# GTStoppuhr.net
KiCad netlist of a schematic drawn in EasyEDA Pro
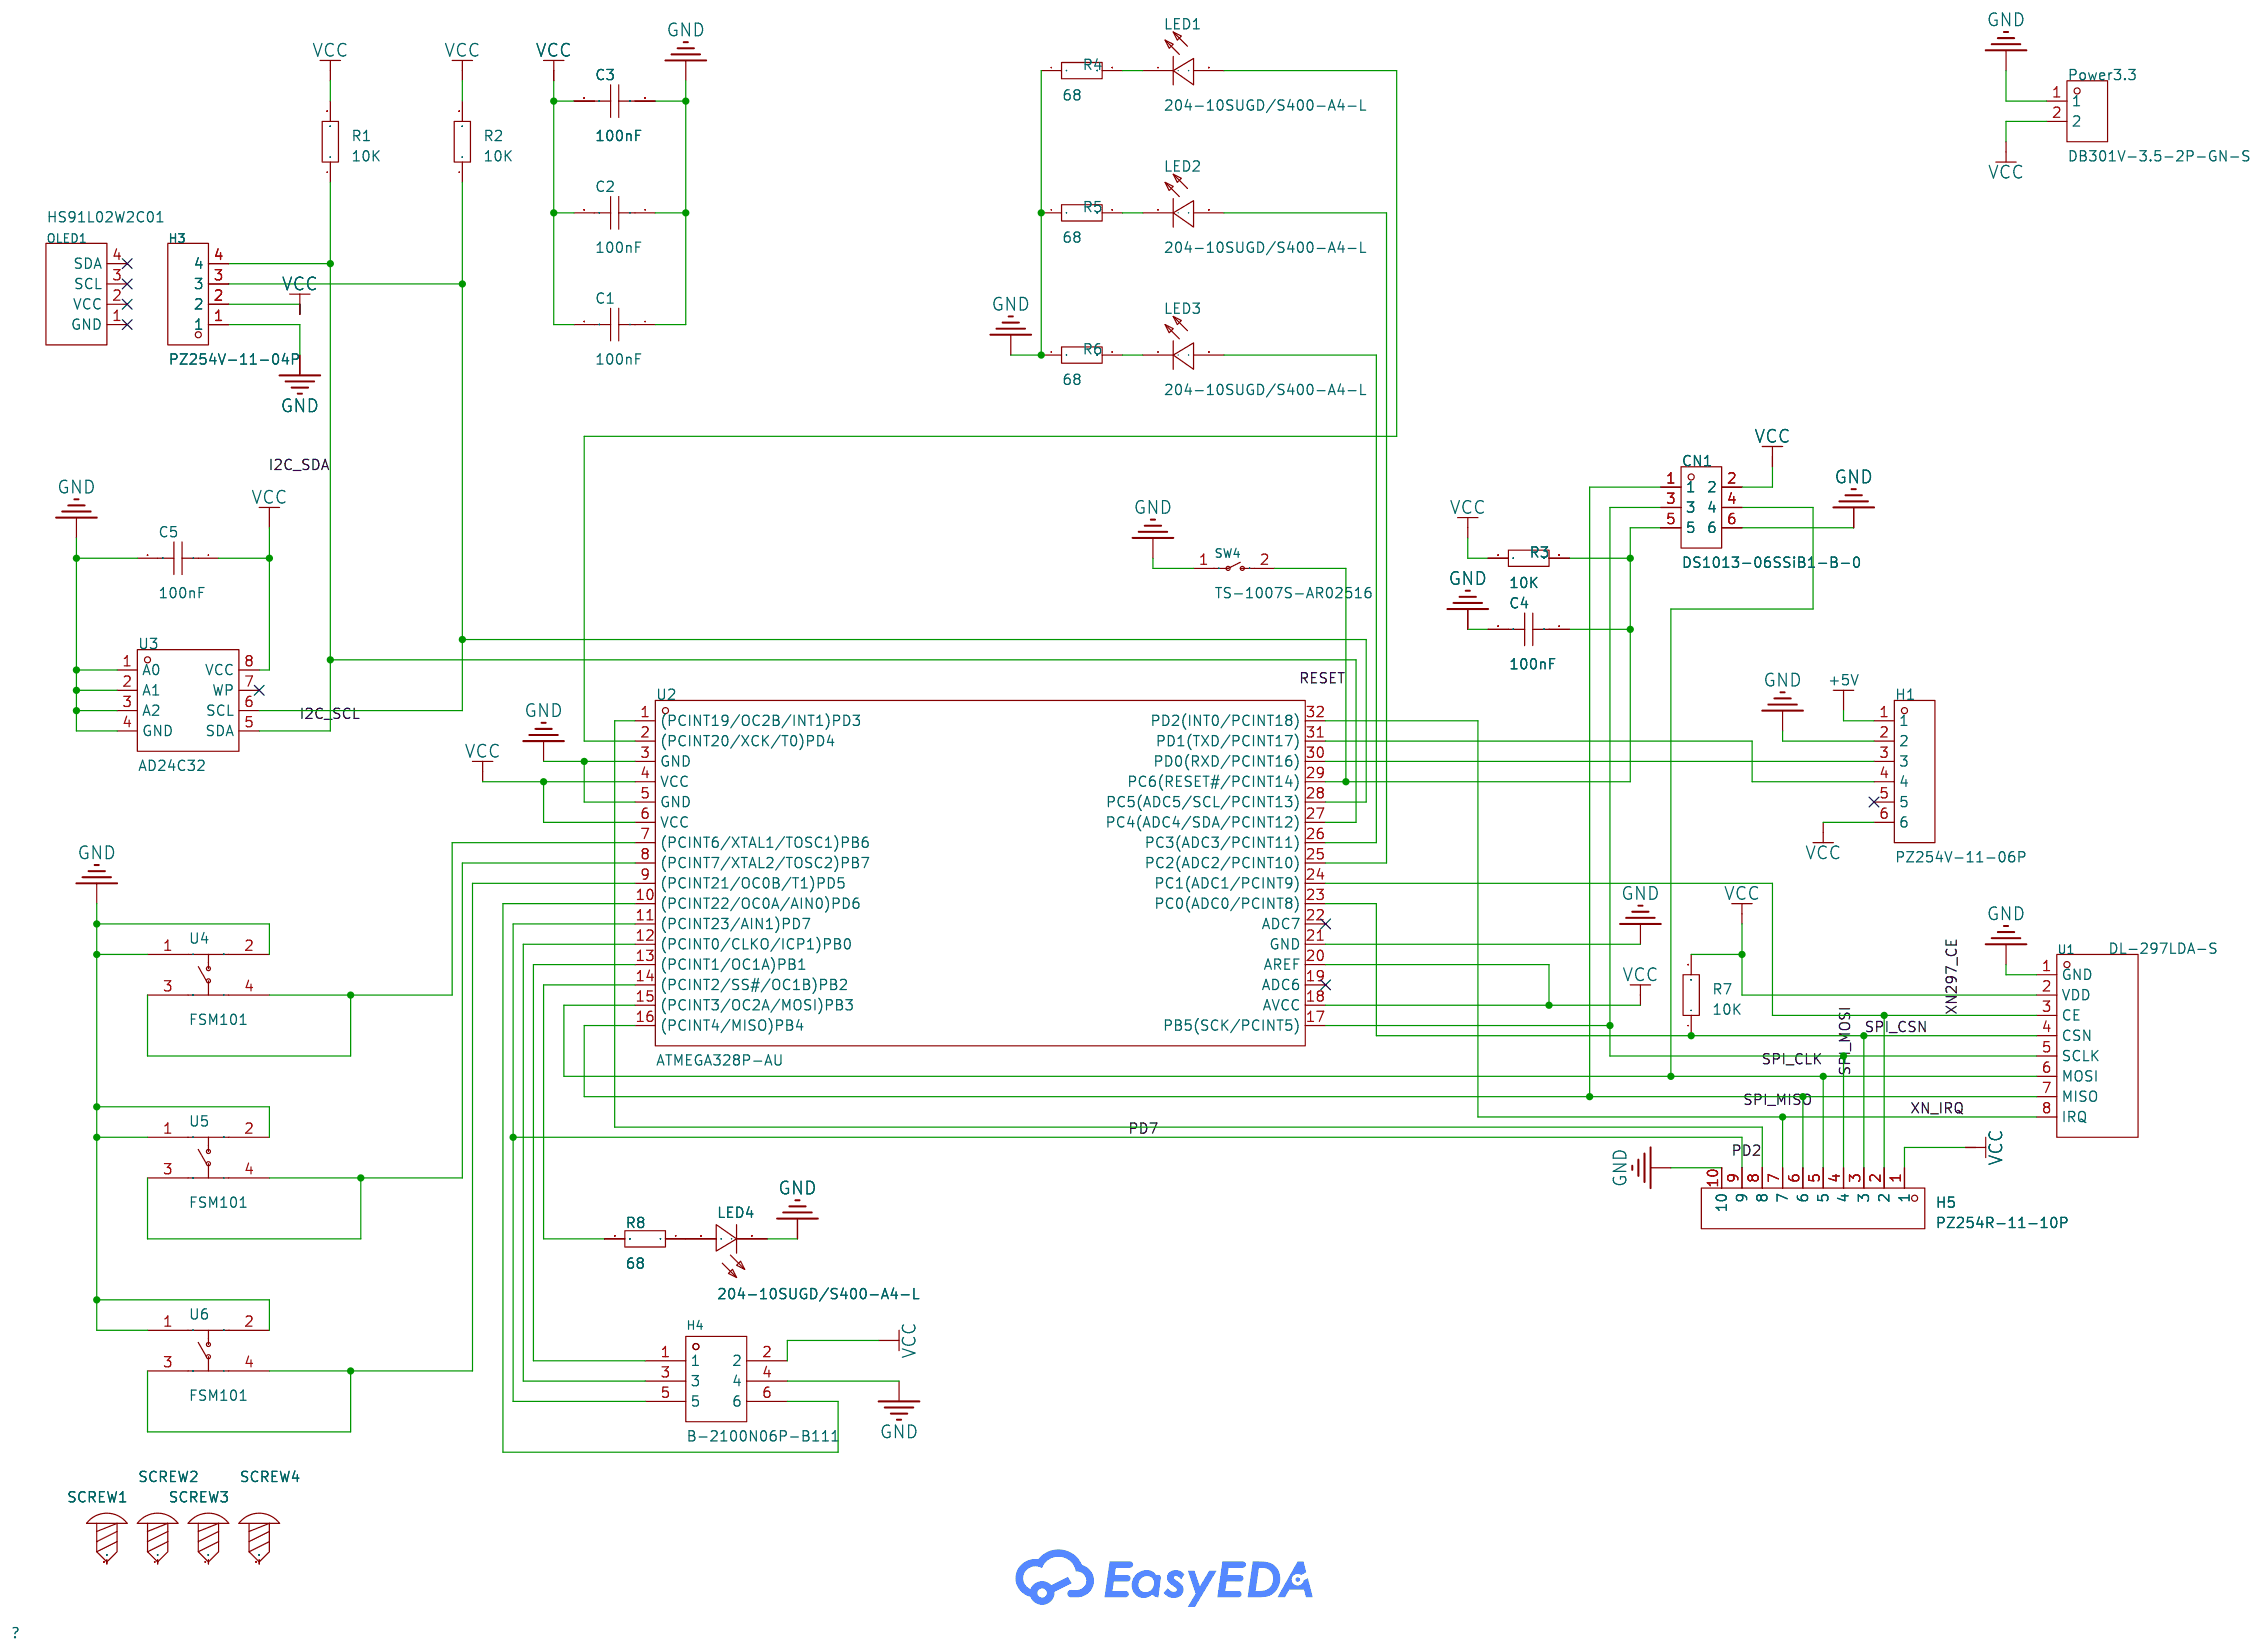
[diagram p0: schematic sheet]

(export (version "E")
  (design (tool "Eeschema 10.0.6"))
  (components
    (comp (ref "C1")
      (value "100nF")
      (footprint "easyedapro:C0603")
      (libsource (lib "easyedapro") (part "CAP"))
    )
    (comp (ref "C2")
      (value "100nF")
      (footprint "easyedapro:C0603")
      (libsource (lib "easyedapro") (part "CAP"))
    )
    (comp (ref "C3")
      (value "100nF")
      (footprint "easyedapro:C0603")
      (libsource (lib "easyedapro") (part "CAP"))
    )
    (comp (ref "C4")
      (value "100nF")
      (footprint "easyedapro:C0603")
      (libsource (lib "easyedapro") (part "CAP"))
    )
    (comp (ref "C5")
      (value "100nF")
      (footprint "easyedapro:C0603")
      (libsource (lib "easyedapro") (part "CAP"))
    )
    (comp (ref "CN1")
      (value "DS1013-06SSiB1-B-0")
      (footprint "easyedapro:IDC-TH_6P-P2.54_DS1013-06SSIB1-B-0")
      (fields (field (name "Manufacturer") "CONNFLY"))
      (libsource (lib "easyedapro") (part "DS1013-06SSIB1-B-0"))
    )
    (comp (ref "H1")
      (value "PZ254V-11-06P")
      (footprint "easyedapro:HDR-TH_6P-P2.54-V-M")
      (fields (field (name "Manufacturer") "XFCN(兴飞)"))
      (libsource (lib "easyedapro") (part "PZ254V-11-06P"))
    )
    (comp (ref "H3")
      (value "PZ254V-11-04P")
      (footprint "easyedapro:HDR-TH_4P-P2.54-V-M")
      (fields (field (name "Manufacturer") "XFCN(兴飞)"))
      (libsource (lib "easyedapro") (part "PZ254V-11-04P_C2691448"))
    )
    (comp (ref "H4")
      (value "B-2100N06P-B111")
      (footprint "easyedapro:HDR-SMD_6P-P2.54-V-M-R2-C3-S2.54-LS7.3")
      (fields (field (name "Manufacturer") "Ckmtw(灿科盟)"))
      (libsource (lib "easyedapro") (part "210SMT-2*3P Gold-plated black"))
    )
    (comp (ref "H5")
      (value "PZ254R-11-10P")
      (footprint "easyedapro:HDR-TH_10P-P2.54-H-M-W10.4")
      (fields (field (name "Manufacturer") "XFCN(兴飞)"))
      (libsource (lib "easyedapro") (part "PZ254R-11-10P"))
    )
    (comp (ref "LED1")
      (value "204-10SUGD/S400-A4-L")
      (footprint "easyedapro:LED-TH_BD3.9-P2.54-RD")
      (fields (field (name "Manufacturer") "EVERLIGHT(亿光)"))
      (libsource (lib "easyedapro") (part "204-10SUGD/S400-A4-L"))
    )
    (comp (ref "LED2")
      (value "204-10SUGD/S400-A4-L")
      (footprint "easyedapro:LED-TH_BD3.9-P2.54-RD")
      (fields (field (name "Manufacturer") "EVERLIGHT(亿光)"))
      (libsource (lib "easyedapro") (part "204-10SUGD/S400-A4-L"))
    )
    (comp (ref "LED3")
      (value "204-10SUGD/S400-A4-L")
      (footprint "easyedapro:LED-TH_BD3.9-P2.54-RD")
      (fields (field (name "Manufacturer") "EVERLIGHT(亿光)"))
      (libsource (lib "easyedapro") (part "204-10SUGD/S400-A4-L"))
    )
    (comp (ref "LED4")
      (value "204-10SUGD/S400-A4-L")
      (footprint "easyedapro:LED-TH_BD3.9-P2.54-RD")
      (fields (field (name "Manufacturer") "EVERLIGHT(亿光)"))
      (libsource (lib "easyedapro") (part "204-10SUGD/S400-A4-L"))
    )
    (comp (ref "OLED1")
      (value "HS91L02W2C01")
      (footprint "easyedapro:OLED-TH_L38.0-W12.0_HS91L02W2C01")
      (fields (field (name "Manufacturer") "HS(汉昇)"))
      (libsource (lib "easyedapro") (part "HS91L02W2C01"))
    )
    (comp (ref "Power3.3")
      (value "DB301V-3.5-2P-GN-S")
      (footprint "easyedapro:CONN-TH_2P-P3.50_DIBO_DB127S-3.5-2P-GN")
      (fields (field (name "Manufacturer") "DORABO(地博电气)"))
      (libsource (lib "easyedapro") (part "DB127S-3.5-2P-GN"))
    )
    (comp (ref "R1") (value "10K") (footprint "easyedapro:R0603") (libsource (lib "easyedapro") (part "Res")))
    (comp (ref "R2") (value "10K") (footprint "easyedapro:R0603") (libsource (lib "easyedapro") (part "Res")))
    (comp (ref "R3") (value "10K") (footprint "easyedapro:R0603") (libsource (lib "easyedapro") (part "Res")))
    (comp (ref "R4") (value "68") (footprint "easyedapro:R0603") (libsource (lib "easyedapro") (part "Res")))
    (comp (ref "R5") (value "68") (footprint "easyedapro:R0603") (libsource (lib "easyedapro") (part "Res")))
    (comp (ref "R6") (value "68") (footprint "easyedapro:R0603") (libsource (lib "easyedapro") (part "Res")))
    (comp (ref "R7") (value "10K") (footprint "easyedapro:R0603") (libsource (lib "easyedapro") (part "Res")))
    (comp (ref "R8") (value "68") (footprint "easyedapro:R0603") (libsource (lib "easyedapro") (part "Res")))
    (comp (ref "SCREW1")
      (value "~")
      (footprint "easyedapro:Screw-Hole-M4")
      (description "Screw-Hole-M4")
      (libsource (lib "easyedapro") (part "Screw-Hole"))
    )
    (comp (ref "SCREW2")
      (value "~")
      (footprint "easyedapro:Screw-Hole-M4")
      (description "Screw-Hole-M4")
      (libsource (lib "easyedapro") (part "Screw-Hole"))
    )
    (comp (ref "SCREW3")
      (value "~")
      (footprint "easyedapro:Screw-Hole-M4")
      (description "Screw-Hole-M4")
      (libsource (lib "easyedapro") (part "Screw-Hole"))
    )
    (comp (ref "SCREW4")
      (value "~")
      (footprint "easyedapro:Screw-Hole-M4")
      (description "Screw-Hole-M4")
      (libsource (lib "easyedapro") (part "Screw-Hole"))
    )
    (comp (ref "SW4")
      (value "TS-1007S-AR02516")
      (footprint "easyedapro:SW-SMD_L6.1-W3.6-LS7.9")
      (fields (field (name "Manufacturer") "XUNPU(讯普)"))
      (libsource (lib "easyedapro") (part "TS-1007S-AR02516"))
    )
    (comp (ref "U1")
      (value "DL-297LDA-S")
      (footprint "easyedapro:WIRELM-SMD_DL-297LDA-S")
      (fields (field (name "Manufacturer") "DreamLNK(骏晔科技)"))
      (libsource (lib "easyedapro") (part "DL-297LDA-S"))
    )
    (comp (ref "U2")
      (value "ATMEGA328P-AU")
      (footprint "easyedapro:TQFP-32_L7.0-W7.0-P0.80-LS9.0-BL")
      (fields (field (name "Manufacturer") "MICROCHIP(美国微芯)"))
      (libsource (lib "easyedapro") (part "ATMEGA328P-AU"))
    )
    (comp (ref "U3")
      (value "AD24C32")
      (footprint "easyedapro:SOIC-8_L4.9-W3.9-P1.27-LS6.2-BL")
      (fields (field (name "Manufacturer") "IDCHIP(英锐芯)"))
      (libsource (lib "easyedapro") (part "AD24C32"))
    )
    (comp (ref "U4")
      (value "FSM101")
      (footprint "easyedapro:SW-TH_4P-L12.0-W12.0-P5.00-LS12.5")
      (fields (field (name "Manufacturer") "TE Connectivity(泰科电子)"))
      (libsource (lib "easyedapro") (part "FSM101"))
    )
    (comp (ref "U5")
      (value "FSM101")
      (footprint "easyedapro:SW-TH_4P-L12.0-W12.0-P5.00-LS12.5")
      (fields (field (name "Manufacturer") "TE Connectivity(泰科电子)"))
      (libsource (lib "easyedapro") (part "FSM101"))
    )
    (comp (ref "U6")
      (value "FSM101")
      (footprint "easyedapro:SW-TH_4P-L12.0-W12.0-P5.00-LS12.5")
      (fields (field (name "Manufacturer") "TE Connectivity(泰科电子)"))
      (libsource (lib "easyedapro") (part "FSM101"))
    )
  )
  (nets
    (net (code "1") (name "+5V") (class "Default")
      (node (ref "H1") (pin "1") (pinfunction "1_1") (pintype "unspecified"))
    )
    (net (code "2") (name "/I2C_SCL") (class "Default")
      (node (ref "H3") (pin "3") (pinfunction "3_3") (pintype "input"))
      (node (ref "R2") (pin "1") (pinfunction "1_1") (pintype "input"))
      (node (ref "U2") (pin "28") (pinfunction "PC5(ADC5/SCL/PCINT13)_28") (pintype "unspecified"))
      (node (ref "U3") (pin "6") (pinfunction "SCL_6") (pintype "unspecified"))
    )
    (net (code "3") (name "/I2C_SDA") (class "Default")
      (node (ref "H3") (pin "4") (pinfunction "4_4") (pintype "input"))
      (node (ref "R1") (pin "1") (pinfunction "1_1") (pintype "input"))
      (node (ref "U2") (pin "27") (pinfunction "PC4(ADC4/SDA/PCINT12)_27") (pintype "unspecified"))
      (node (ref "U3") (pin "5") (pinfunction "SDA_5") (pintype "unspecified"))
    )
    (net (code "4") (name "/PD2") (class "Default")
      (node (ref "H5") (pin "8") (pinfunction "8_8") (pintype "unspecified"))
      (node (ref "U2") (pin "1") (pinfunction "(PCINT19/OC2B/INT1)PD3_1") (pintype "unspecified"))
    )
    (net (code "5") (name "/PD7") (class "Default")
      (node (ref "H4") (pin "5") (pinfunction "5_5") (pintype "input"))
      (node (ref "H5") (pin "9") (pinfunction "9_9") (pintype "unspecified"))
      (node (ref "U2") (pin "11") (pinfunction "(PCINT23/AIN1)PD7_11") (pintype "unspecified"))
    )
    (net (code "6") (name "/RESET") (class "Default")
      (node (ref "C4") (pin "1") (pinfunction "1_1") (pintype "input"))
      (node (ref "CN1") (pin "5") (pinfunction "5_5") (pintype "unspecified"))
      (node (ref "R3") (pin "2") (pinfunction "2_2") (pintype "input"))
      (node (ref "SW4") (pin "2") (pinfunction "2_2") (pintype "input"))
      (node (ref "U2") (pin "29") (pinfunction "PC6(RESET#/PCINT14)_29") (pintype "unspecified"))
    )
    (net (code "7") (name "/SPI_CLK") (class "Default")
      (node (ref "CN1") (pin "3") (pinfunction "3_3") (pintype "unspecified"))
      (node (ref "H5") (pin "4") (pinfunction "4_4") (pintype "unspecified"))
      (node (ref "U1") (pin "5") (pinfunction "SCLK_5") (pintype "input"))
      (node (ref "U2") (pin "17") (pinfunction "PB5(SCK/PCINT5)_17") (pintype "unspecified"))
    )
    (net (code "8") (name "/SPI_CSN") (class "Default")
      (node (ref "H5") (pin "3") (pinfunction "3_3") (pintype "unspecified"))
      (node (ref "R7") (pin "1") (pinfunction "1_1") (pintype "input"))
      (node (ref "U1") (pin "4") (pinfunction "CSN_4") (pintype "input"))
      (node (ref "U2") (pin "23") (pinfunction "PC0(ADC0/PCINT8)_23") (pintype "unspecified"))
    )
    (net (code "9") (name "/SPI_MISO") (class "Default")
      (node (ref "CN1") (pin "1") (pinfunction "1_1") (pintype "unspecified"))
      (node (ref "H5") (pin "6") (pinfunction "6_6") (pintype "unspecified"))
      (node (ref "U1") (pin "7") (pinfunction "MISO_7") (pintype "input"))
      (node (ref "U2") (pin "16") (pinfunction "(PCINT4/MISO)PB4_16") (pintype "unspecified"))
    )
    (net (code "10") (name "/SPI_MOSI") (class "Default")
      (node (ref "CN1") (pin "4") (pinfunction "4_4") (pintype "unspecified"))
      (node (ref "H5") (pin "5") (pinfunction "5_5") (pintype "unspecified"))
      (node (ref "U1") (pin "6") (pinfunction "MOSI_6") (pintype "input"))
      (node (ref "U2") (pin "15") (pinfunction "(PCINT3/OC2A/MOSI)PB3_15") (pintype "unspecified"))
    )
    (net (code "11") (name "/XN297_CE") (class "Default")
      (node (ref "H5") (pin "2") (pinfunction "2_2") (pintype "unspecified"))
      (node (ref "U1") (pin "3") (pinfunction "CE_3") (pintype "input"))
      (node (ref "U2") (pin "24") (pinfunction "PC1(ADC1/PCINT9)_24") (pintype "unspecified"))
    )
    (net (code "12") (name "/XN_IRQ") (class "Default")
      (node (ref "H5") (pin "7") (pinfunction "7_7") (pintype "unspecified"))
      (node (ref "U1") (pin "8") (pinfunction "IRQ_8") (pintype "input"))
      (node (ref "U2") (pin "32") (pinfunction "PD2(INT0/PCINT18)_32") (pintype "unspecified"))
    )
    (net (code "13") (name "GND") (class "Default")
      (node (ref "C1") (pin "1") (pinfunction "1_1") (pintype "input"))
      (node (ref "C2") (pin "1") (pinfunction "1_1") (pintype "input"))
      (node (ref "C3") (pin "2") (pinfunction "2_2") (pintype "input"))
      (node (ref "C4") (pin "2") (pinfunction "2_2") (pintype "input"))
      (node (ref "C5") (pin "2") (pinfunction "2_2") (pintype "input"))
      (node (ref "CN1") (pin "6") (pinfunction "6_6") (pintype "unspecified"))
      (node (ref "H1") (pin "2") (pinfunction "2_2") (pintype "unspecified"))
      (node (ref "H3") (pin "1") (pinfunction "1_1") (pintype "input"))
      (node (ref "H4") (pin "4") (pinfunction "4_4") (pintype "input"))
      (node (ref "H5") (pin "10") (pinfunction "10_10") (pintype "unspecified"))
      (node (ref "LED4") (pin "1") (pinfunction "-_1") (pintype "input"))
      (node (ref "Power3.3") (pin "1") (pinfunction "1_1") (pintype "unspecified"))
      (node (ref "R4") (pin "1") (pinfunction "1_1") (pintype "input"))
      (node (ref "R5") (pin "1") (pinfunction "1_1") (pintype "input"))
      (node (ref "R6") (pin "1") (pinfunction "1_1") (pintype "input"))
      (node (ref "SW4") (pin "1") (pinfunction "1_1") (pintype "input"))
      (node (ref "U1") (pin "1") (pinfunction "GND_1") (pintype "input"))
      (node (ref "U2") (pin "21") (pinfunction "GND_21") (pintype "unspecified"))
      (node (ref "U2") (pin "3") (pinfunction "GND_3") (pintype "unspecified"))
      (node (ref "U2") (pin "5") (pinfunction "GND_5") (pintype "unspecified"))
      (node (ref "U3") (pin "1") (pinfunction "A0_1") (pintype "unspecified"))
      (node (ref "U3") (pin "2") (pinfunction "A1_2") (pintype "unspecified"))
      (node (ref "U3") (pin "3") (pinfunction "A2_3") (pintype "unspecified"))
      (node (ref "U3") (pin "4") (pinfunction "GND_4") (pintype "unspecified"))
      (node (ref "U4") (pin "1") (pinfunction "1_1") (pintype "unspecified"))
      (node (ref "U4") (pin "2") (pinfunction "2_2") (pintype "unspecified"))
      (node (ref "U5") (pin "1") (pinfunction "1_1") (pintype "unspecified"))
      (node (ref "U5") (pin "2") (pinfunction "2_2") (pintype "unspecified"))
      (node (ref "U6") (pin "1") (pinfunction "1_1") (pintype "unspecified"))
      (node (ref "U6") (pin "2") (pinfunction "2_2") (pintype "unspecified"))
    )
    (net (code "14") (name "Net-(LED1-+)") (class "Default")
      (node (ref "LED1") (pin "2") (pinfunction "+_2") (pintype "input"))
      (node (ref "U2") (pin "2") (pinfunction "(PCINT20/XCK/T0)PD4_2") (pintype "unspecified"))
    )
    (net (code "15") (name "Net-(LED1--)") (class "Default")
      (node (ref "LED1") (pin "1") (pinfunction "-_1") (pintype "input"))
      (node (ref "R4") (pin "2") (pinfunction "2_2") (pintype "input"))
    )
    (net (code "16") (name "Net-(LED2-+)") (class "Default")
      (node (ref "LED2") (pin "2") (pinfunction "+_2") (pintype "input"))
      (node (ref "U2") (pin "25") (pinfunction "PC2(ADC2/PCINT10)_25") (pintype "unspecified"))
    )
    (net (code "17") (name "Net-(LED2--)") (class "Default")
      (node (ref "LED2") (pin "1") (pinfunction "-_1") (pintype "input"))
      (node (ref "R5") (pin "2") (pinfunction "2_2") (pintype "input"))
    )
    (net (code "18") (name "Net-(LED3-+)") (class "Default")
      (node (ref "LED3") (pin "2") (pinfunction "+_2") (pintype "input"))
      (node (ref "U2") (pin "26") (pinfunction "PC3(ADC3/PCINT11)_26") (pintype "unspecified"))
    )
    (net (code "19") (name "Net-(LED3--)") (class "Default")
      (node (ref "LED3") (pin "1") (pinfunction "-_1") (pintype "input"))
      (node (ref "R6") (pin "2") (pinfunction "2_2") (pintype "input"))
    )
    (net (code "20") (name "Net-(LED4-+)") (class "Default")
      (node (ref "LED4") (pin "2") (pinfunction "+_2") (pintype "input"))
      (node (ref "R8") (pin "1") (pinfunction "1_1") (pintype "input"))
    )
    (net (code "21") (name "Net-(U2-(PCINT0{slash}CLKO{slash}ICP1)PB0)") (class "Default")
      (node (ref "H4") (pin "3") (pinfunction "3_3") (pintype "input"))
      (node (ref "U2") (pin "12") (pinfunction "(PCINT0/CLKO/ICP1)PB0_12") (pintype "unspecified"))
    )
    (net (code "22") (name "Net-(U2-(PCINT1{slash}OC1A)PB1)") (class "Default")
      (node (ref "H4") (pin "1") (pinfunction "1_1") (pintype "input"))
      (node (ref "U2") (pin "13") (pinfunction "(PCINT1/OC1A)PB1_13") (pintype "unspecified"))
    )
    (net (code "23") (name "Net-(U2-(PCINT2{slash}SS#{slash}OC1B)PB2)") (class "Default")
      (node (ref "R8") (pin "2") (pinfunction "2_2") (pintype "input"))
      (node (ref "U2") (pin "14") (pinfunction "(PCINT2/SS#/OC1B)PB2_14") (pintype "unspecified"))
    )
    (net (code "24") (name "Net-(U2-(PCINT6{slash}XTAL1{slash}TOSC1)PB6)") (class "Default")
      (node (ref "U2") (pin "7") (pinfunction "(PCINT6/XTAL1/TOSC1)PB6_7") (pintype "unspecified"))
      (node (ref "U4") (pin "3") (pinfunction "3_3") (pintype "unspecified"))
      (node (ref "U4") (pin "4") (pinfunction "4_4") (pintype "unspecified"))
    )
    (net (code "25") (name "Net-(U2-(PCINT7{slash}XTAL2{slash}TOSC2)PB7)") (class "Default")
      (node (ref "U2") (pin "8") (pinfunction "(PCINT7/XTAL2/TOSC2)PB7_8") (pintype "unspecified"))
      (node (ref "U5") (pin "3") (pinfunction "3_3") (pintype "unspecified"))
      (node (ref "U5") (pin "4") (pinfunction "4_4") (pintype "unspecified"))
    )
    (net (code "26") (name "Net-(U2-(PCINT21{slash}OC0B{slash}T1)PD5)") (class "Default")
      (node (ref "U2") (pin "9") (pinfunction "(PCINT21/OC0B/T1)PD5_9") (pintype "unspecified"))
      (node (ref "U6") (pin "3") (pinfunction "3_3") (pintype "unspecified"))
      (node (ref "U6") (pin "4") (pinfunction "4_4") (pintype "unspecified"))
    )
    (net (code "27") (name "Net-(U2-(PCINT22{slash}OC0A{slash}AIN0)PD6)") (class "Default")
      (node (ref "H4") (pin "6") (pinfunction "6_6") (pintype "input"))
      (node (ref "U2") (pin "10") (pinfunction "(PCINT22/OC0A/AIN0)PD6_10") (pintype "unspecified"))
    )
    (net (code "28") (name "Net-(U2-PD0(RXD{slash}PCINT16))") (class "Default")
      (node (ref "H1") (pin "3") (pinfunction "3_3") (pintype "unspecified"))
      (node (ref "U2") (pin "30") (pinfunction "PD0(RXD/PCINT16)_30") (pintype "unspecified"))
    )
    (net (code "29") (name "Net-(U2-PD1(TXD{slash}PCINT17))") (class "Default")
      (node (ref "H1") (pin "4") (pinfunction "4_4") (pintype "unspecified"))
      (node (ref "U2") (pin "31") (pinfunction "PD1(TXD/PCINT17)_31") (pintype "unspecified"))
    )
    (net (code "30") (name "VCC") (class "Default")
      (node (ref "C1") (pin "2") (pinfunction "2_2") (pintype "input"))
      (node (ref "C2") (pin "2") (pinfunction "2_2") (pintype "input"))
      (node (ref "C3") (pin "1") (pinfunction "1_1") (pintype "input"))
      (node (ref "C5") (pin "1") (pinfunction "1_1") (pintype "input"))
      (node (ref "CN1") (pin "2") (pinfunction "2_2") (pintype "unspecified"))
      (node (ref "H1") (pin "6") (pinfunction "6_6") (pintype "unspecified"))
      (node (ref "H3") (pin "2") (pinfunction "2_2") (pintype "input"))
      (node (ref "H4") (pin "2") (pinfunction "2_2") (pintype "input"))
      (node (ref "H5") (pin "1") (pinfunction "1_1") (pintype "unspecified"))
      (node (ref "Power3.3") (pin "2") (pinfunction "2_2") (pintype "unspecified"))
      (node (ref "R1") (pin "2") (pinfunction "2_2") (pintype "input"))
      (node (ref "R2") (pin "2") (pinfunction "2_2") (pintype "input"))
      (node (ref "R3") (pin "1") (pinfunction "1_1") (pintype "input"))
      (node (ref "R7") (pin "2") (pinfunction "2_2") (pintype "input"))
      (node (ref "U1") (pin "2") (pinfunction "VDD_2") (pintype "input"))
      (node (ref "U2") (pin "18") (pinfunction "AVCC_18") (pintype "unspecified"))
      (node (ref "U2") (pin "20") (pinfunction "AREF_20") (pintype "unspecified"))
      (node (ref "U2") (pin "4") (pinfunction "VCC_4") (pintype "unspecified"))
      (node (ref "U2") (pin "6") (pinfunction "VCC_6") (pintype "unspecified"))
      (node (ref "U3") (pin "8") (pinfunction "VCC_8") (pintype "unspecified"))
    )
    (net (code "31") (name "unconnected-(H1-Pad5)") (class "Default")
      (node (ref "H1") (pin "5") (pinfunction "5_5") (pintype "unspecified+no_connect"))
    )
    (net (code "32") (name "unconnected-(OLED1-GND-Pad1)") (class "Default")
      (node (ref "OLED1") (pin "1") (pinfunction "GND_1") (pintype "input+no_connect"))
    )
    (net (code "33") (name "unconnected-(OLED1-SCL-Pad3)") (class "Default")
      (node (ref "OLED1") (pin "3") (pinfunction "SCL_3") (pintype "input+no_connect"))
    )
    (net (code "34") (name "unconnected-(OLED1-SDA-Pad4)") (class "Default")
      (node (ref "OLED1") (pin "4") (pinfunction "SDA_4") (pintype "input+no_connect"))
    )
    (net (code "35") (name "unconnected-(OLED1-VCC-Pad2)") (class "Default")
      (node (ref "OLED1") (pin "2") (pinfunction "VCC_2") (pintype "input+no_connect"))
    )
    (net (code "36") (name "unconnected-(SCREW1-Pad1)") (class "Default")
      (node (ref "SCREW1") (pin "1") (pinfunction "1_1") (pintype "input"))
    )
    (net (code "37") (name "unconnected-(SCREW2-Pad1)") (class "Default")
      (node (ref "SCREW2") (pin "1") (pinfunction "1_1") (pintype "input"))
    )
    (net (code "38") (name "unconnected-(SCREW3-Pad1)") (class "Default")
      (node (ref "SCREW3") (pin "1") (pinfunction "1_1") (pintype "input"))
    )
    (net (code "39") (name "unconnected-(SCREW4-Pad1)") (class "Default")
      (node (ref "SCREW4") (pin "1") (pinfunction "1_1") (pintype "input"))
    )
    (net (code "40") (name "unconnected-(U2-ADC6-Pad19)") (class "Default")
      (node (ref "U2") (pin "19") (pinfunction "ADC6_19") (pintype "unspecified+no_connect"))
    )
    (net (code "41") (name "unconnected-(U2-ADC7-Pad22)") (class "Default")
      (node (ref "U2") (pin "22") (pinfunction "ADC7_22") (pintype "unspecified+no_connect"))
    )
    (net (code "42") (name "unconnected-(U3-WP-Pad7)") (class "Default")
      (node (ref "U3") (pin "7") (pinfunction "WP_7") (pintype "unspecified+no_connect"))
    )
  )
)
